# 65c02.net
KiCad netlist of a schematic drawn in Altium Designer
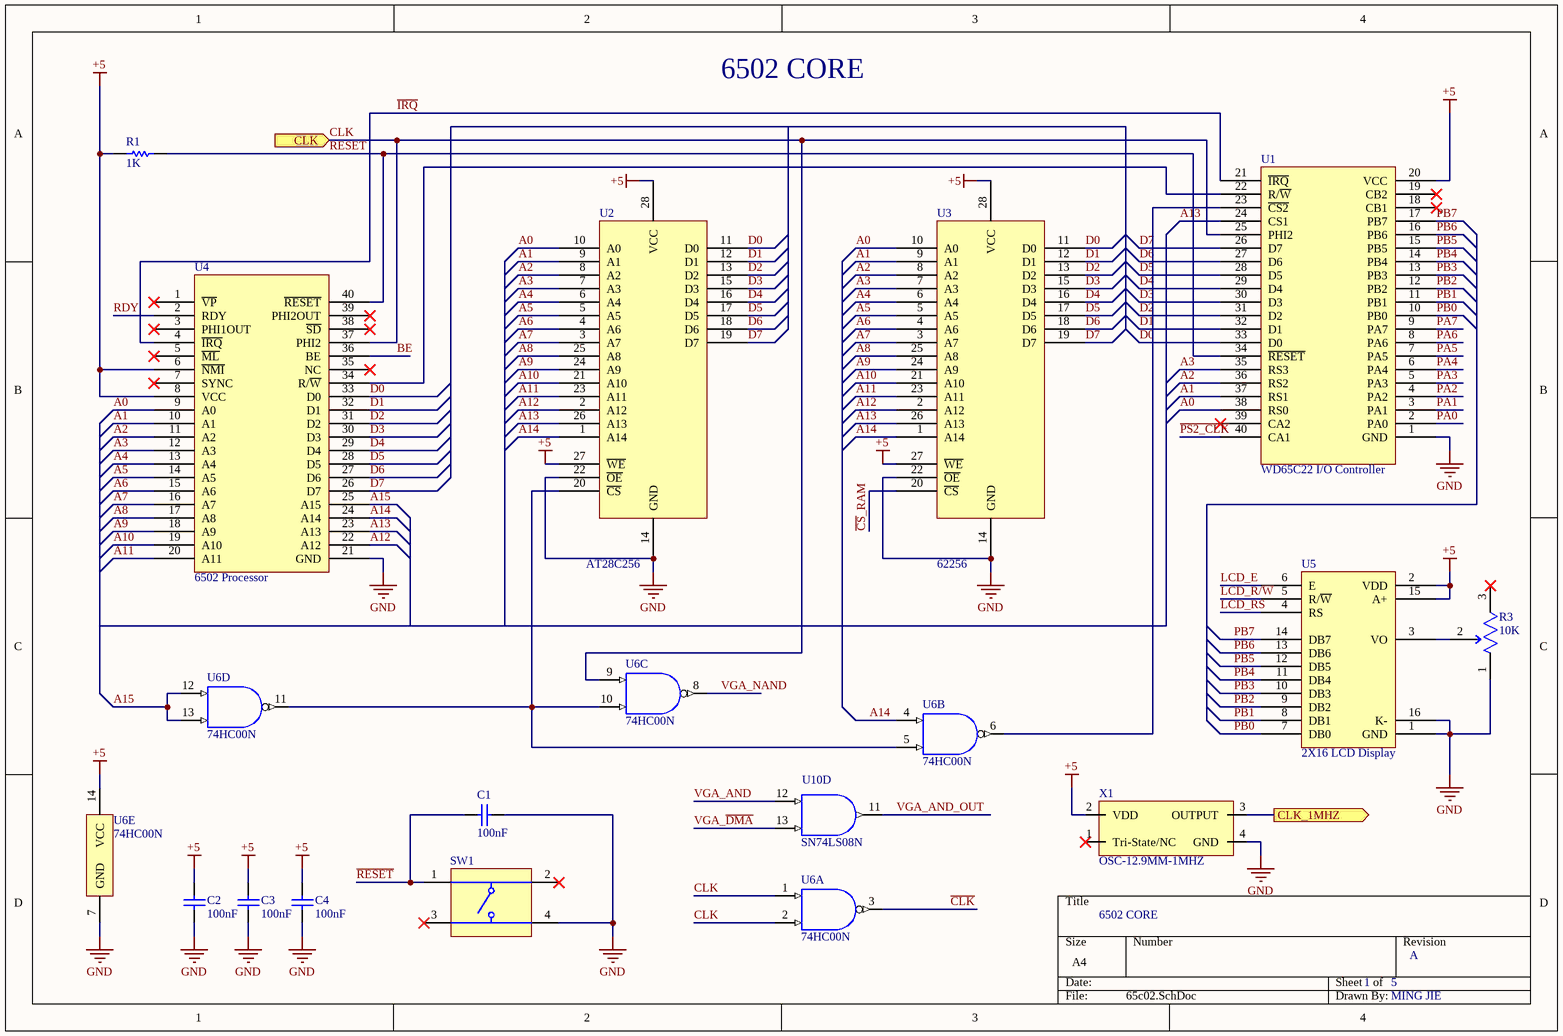
[diagram p0: 65c02.SchDoc]

(export (version "E")
  (design (tool "Eeschema 10.0.6"))
  (components
    (comp (ref "C1")
      (value "GRM21BR71H104KA01L")
      (footprint "CAPC2013X135X45ML10T25")
      (description "Chip Capacitor, 0.1 uF, +/- 10%, 50 V, -55 to 125 degC, 0805 (2012 Metric), RoHS, Tape and Reel")
      (fields
        (field (name "VOLTAGE") "50V")
        (field (name "CAPACITANCE") "100nF")
        (field (name "TOLERANCE") "10%")
      )
      (libsource (lib "Altium Content Vault") (part "CAP-NP-2"))
    )
    (comp (ref "C2")
      (value "GRM21BR71H104KA01L")
      (footprint "CAPC2013X135X45ML10T25")
      (description "Chip Capacitor, 0.1 uF, +/- 10%, 50 V, -55 to 125 degC, 0805 (2012 Metric), RoHS, Tape and Reel")
      (fields
        (field (name "VOLTAGE") "50V")
        (field (name "CAPACITANCE") "100nF")
        (field (name "TOLERANCE") "10%")
      )
      (libsource (lib "Altium Content Vault") (part "CAP-NP-2"))
    )
    (comp (ref "C3")
      (value "GRM21BR71H104KA01L")
      (footprint "CAPC2013X135X45ML10T25")
      (description "Chip Capacitor, 0.1 uF, +/- 10%, 50 V, -55 to 125 degC, 0805 (2012 Metric), RoHS, Tape and Reel")
      (fields
        (field (name "VOLTAGE") "50V")
        (field (name "CAPACITANCE") "100nF")
        (field (name "TOLERANCE") "10%")
      )
      (libsource (lib "Altium Content Vault") (part "CAP-NP-2"))
    )
    (comp (ref "C4")
      (value "GRM21BR71H104KA01L")
      (footprint "CAPC2013X135X45ML10T25")
      (description "Chip Capacitor, 0.1 uF, +/- 10%, 50 V, -55 to 125 degC, 0805 (2012 Metric), RoHS, Tape and Reel")
      (fields
        (field (name "VOLTAGE") "50V")
        (field (name "CAPACITANCE") "100nF")
        (field (name "TOLERANCE") "10%")
      )
      (libsource (lib "Altium Content Vault") (part "CAP-NP-2"))
    )
    (comp (ref "R1")
      (value "CRCW08051K00FKEA")
      (footprint "RESC2013X50X30NL20T20")
      (fields (field (name "MANUFACTURER") "Vishay Dale") (field (name "RESISTANCE") "1K"))
      (libsource (lib "Altium Content Vault") (part "RES"))
    )
    (comp (ref "R3")
      (value "3296W-1-103RLF")
      (footprint "FP-3296W-MFG")
      (description "TRIMMER 10K OHM 0.5W PC PIN TOP")
      (fields (field (name "RESISTANCE") "10K") (field (name "TOLERANCE") "10%"))
      (libsource (lib "Altium Content Vault") (part "194907ebf2981c0cdd5d9631a0af656"))
    )
    (comp (ref "SW1")
      (value "K2-1102SP-C4SC-04")
      (footprint "TECO-FSM4JSMA_V")
      (description "Swicth, SPST, 24 V, -35 to 85 degC, 4-Pin SMD, RoHS, Tape and Reel")
      (fields (field (name "MANUFACTURER") "TE Connectivity"))
      (libsource (lib "Altium Content Vault") (part "SW-SPST-4_A"))
    )
    (comp (ref "U1")
      (value "WD65C22 I/O Controller")
      (footprint "PDIP_40")
      (description "WD65C22 PDIP-40, I/O Controller")
      (libsource (lib "6502_lib") (part "WD65C22"))
    )
    (comp (ref "U2")
      (value "AT28C256")
      (footprint "DIP_28")
      (description "Paged Parallel EEPROM AT28C256")
      (libsource (lib "6502_lib") (part "AT28C256"))
    )
    (comp (ref "U3")
      (value "62256")
      (footprint "DIP_28")
      (description "32K x 8, SRAM")
      (libsource (lib "6502_lib") (part "62256"))
    )
    (comp (ref "U4")
      (value "6502 Processor")
      (footprint "PDIP_40")
      (description "WDC 6502 PDIP-40")
      (libsource (lib "6502_lib") (part "WDC65C02"))
    )
    (comp (ref "U5")
      (value "2X16 LCD Display")
      (footprint "LCD_2x16")
      (description "2X16 LCD Display, Parallel input")
      (libsource (lib "6502_lib") (part "LCM1602C"))
    )
    (comp (ref "U6")
      (value "74HC00N")
      (footprint "NXP-SOT27-1-14")
      (description "Quad 2-input NAND gate, CMOS, 2 to 6 V, -40 to 125 degC, 14-Pin DIP (SOT27-1), RoHS, Bulk")
      (fields (field (name "MANUFACTURER") "NXP Semiconductors"))
      (libsource (lib "Altium Content Vault") (part "NXP-74HC00N_HCT00N-DIP-14"))
    )
    (comp (ref "U10")
      (value "SN74LS08N")
      (footprint "N0014A")
      (description "Quadruple 2-Input Positive-AND Gates, N0014A, TUBE")
      (fields
        (field (name "MANUFACTURER") "Texas Instruments")
        (field (name "GENERIC PART NUMBER") "SN74LS08")
      )
      (libsource (lib "Altium Content Vault") (part "TI-AND-4-2IN-14"))
    )
    (comp (ref "X1")
      (value "OSC-12.9MM-1MHZ")
      (footprint "OSC_THT_12-9MM")
      (description "12.9MM x 12.9MM, 1MHz Can Oscillator")
      (libsource (lib "6502_lib") (part "OSC-12.9MM-1MHZ"))
    )
  )
  (nets
    (net (code "1") (name "+5") (class "Default")
      (node (ref "C2") (pin "1") (pinfunction "1_1") (pintype "passive"))
      (node (ref "C3") (pin "1") (pinfunction "1_1") (pintype "passive"))
      (node (ref "C4") (pin "1") (pinfunction "1_1") (pintype "passive"))
      (node (ref "R1") (pin "1") (pinfunction "1_1") (pintype "passive"))
      (node (ref "U1") (pin "20") (pinfunction "VCC_20") (pintype "passive"))
      (node (ref "U2") (pin "27") (pinfunction "~{WE}_27") (pintype "passive"))
      (node (ref "U2") (pin "28") (pinfunction "VCC_28") (pintype "passive"))
      (node (ref "U3") (pin "27") (pinfunction "~{WE}_27") (pintype "passive"))
      (node (ref "U3") (pin "28") (pinfunction "VCC_28") (pintype "passive"))
      (node (ref "U4") (pin "6") (pinfunction "~{NMI}_6") (pintype "passive"))
      (node (ref "U4") (pin "8") (pinfunction "VCC_8") (pintype "passive"))
      (node (ref "U5") (pin "15") (pinfunction "A+_15") (pintype "passive"))
      (node (ref "U5") (pin "2") (pinfunction "VDD_2") (pintype "passive"))
      (node (ref "U6") (pin "14") (pinfunction "VCC_14") (pintype "power_in"))
      (node (ref "X1") (pin "2") (pinfunction "VDD_2") (pintype "passive"))
    )
    (net (code "2") (name "/A0") (class "Default")
      (node (ref "U1") (pin "38") (pinfunction "RS0_38") (pintype "passive"))
      (node (ref "U2") (pin "10") (pinfunction "A0_10") (pintype "passive"))
      (node (ref "U3") (pin "10") (pinfunction "A0_10") (pintype "passive"))
      (node (ref "U4") (pin "9") (pinfunction "A0_9") (pintype "passive"))
    )
    (net (code "3") (name "/A1") (class "Default")
      (node (ref "U1") (pin "37") (pinfunction "RS1_37") (pintype "passive"))
      (node (ref "U2") (pin "9") (pinfunction "A1_9") (pintype "passive"))
      (node (ref "U3") (pin "9") (pinfunction "A1_9") (pintype "passive"))
      (node (ref "U4") (pin "10") (pinfunction "A1_10") (pintype "passive"))
    )
    (net (code "4") (name "/A2") (class "Default")
      (node (ref "U1") (pin "36") (pinfunction "RS2_36") (pintype "passive"))
      (node (ref "U2") (pin "8") (pinfunction "A2_8") (pintype "passive"))
      (node (ref "U3") (pin "8") (pinfunction "A2_8") (pintype "passive"))
      (node (ref "U4") (pin "11") (pinfunction "A2_11") (pintype "passive"))
    )
    (net (code "5") (name "/A3") (class "Default")
      (node (ref "U1") (pin "35") (pinfunction "RS3_35") (pintype "passive"))
      (node (ref "U2") (pin "7") (pinfunction "A3_7") (pintype "passive"))
      (node (ref "U3") (pin "7") (pinfunction "A3_7") (pintype "passive"))
      (node (ref "U4") (pin "12") (pinfunction "A3_12") (pintype "passive"))
    )
    (net (code "6") (name "/A4") (class "Default")
      (node (ref "U2") (pin "6") (pinfunction "A4_6") (pintype "passive"))
      (node (ref "U3") (pin "6") (pinfunction "A4_6") (pintype "passive"))
      (node (ref "U4") (pin "13") (pinfunction "A4_13") (pintype "passive"))
    )
    (net (code "7") (name "/A5") (class "Default")
      (node (ref "U2") (pin "5") (pinfunction "A5_5") (pintype "passive"))
      (node (ref "U3") (pin "5") (pinfunction "A5_5") (pintype "passive"))
      (node (ref "U4") (pin "14") (pinfunction "A5_14") (pintype "passive"))
    )
    (net (code "8") (name "/A6") (class "Default")
      (node (ref "U2") (pin "4") (pinfunction "A6_4") (pintype "passive"))
      (node (ref "U3") (pin "4") (pinfunction "A6_4") (pintype "passive"))
      (node (ref "U4") (pin "15") (pinfunction "A6_15") (pintype "passive"))
    )
    (net (code "9") (name "/A7") (class "Default")
      (node (ref "U2") (pin "3") (pinfunction "A7_3") (pintype "passive"))
      (node (ref "U3") (pin "3") (pinfunction "A7_3") (pintype "passive"))
      (node (ref "U4") (pin "16") (pinfunction "A7_16") (pintype "passive"))
    )
    (net (code "10") (name "/A8") (class "Default")
      (node (ref "U2") (pin "25") (pinfunction "A8_25") (pintype "passive"))
      (node (ref "U3") (pin "25") (pinfunction "A8_25") (pintype "passive"))
      (node (ref "U4") (pin "17") (pinfunction "A8_17") (pintype "passive"))
    )
    (net (code "11") (name "/A9") (class "Default")
      (node (ref "U2") (pin "24") (pinfunction "A9_24") (pintype "passive"))
      (node (ref "U3") (pin "24") (pinfunction "A9_24") (pintype "passive"))
      (node (ref "U4") (pin "18") (pinfunction "A9_18") (pintype "passive"))
    )
    (net (code "12") (name "/A10") (class "Default")
      (node (ref "U2") (pin "21") (pinfunction "A10_21") (pintype "passive"))
      (node (ref "U3") (pin "21") (pinfunction "A10_21") (pintype "passive"))
      (node (ref "U4") (pin "19") (pinfunction "A10_19") (pintype "passive"))
    )
    (net (code "13") (name "/A11") (class "Default")
      (node (ref "U2") (pin "23") (pinfunction "A11_23") (pintype "passive"))
      (node (ref "U3") (pin "23") (pinfunction "A11_23") (pintype "passive"))
      (node (ref "U4") (pin "20") (pinfunction "A11_20") (pintype "passive"))
    )
    (net (code "14") (name "/A12") (class "Default")
      (node (ref "U2") (pin "2") (pinfunction "A12_2") (pintype "passive"))
      (node (ref "U3") (pin "2") (pinfunction "A12_2") (pintype "passive"))
      (node (ref "U4") (pin "22") (pinfunction "A12_22") (pintype "passive"))
    )
    (net (code "15") (name "/A13") (class "Default")
      (node (ref "U1") (pin "24") (pinfunction "CS1_24") (pintype "passive"))
      (node (ref "U2") (pin "26") (pinfunction "A13_26") (pintype "passive"))
      (node (ref "U3") (pin "26") (pinfunction "A13_26") (pintype "passive"))
      (node (ref "U4") (pin "23") (pinfunction "A13_23") (pintype "passive"))
    )
    (net (code "16") (name "/A14") (class "Default")
      (node (ref "U2") (pin "1") (pinfunction "A14_1") (pintype "passive"))
      (node (ref "U3") (pin "1") (pinfunction "A14_1") (pintype "passive"))
      (node (ref "U4") (pin "24") (pinfunction "A14_24") (pintype "passive"))
      (node (ref "U6") (pin "4") (pinfunction "2A_4") (pintype "input"))
    )
    (net (code "17") (name "/A15") (class "Default")
      (node (ref "U4") (pin "25") (pinfunction "A15_25") (pintype "passive"))
      (node (ref "U6") (pin "12") (pinfunction "4A_12") (pintype "input"))
      (node (ref "U6") (pin "13") (pinfunction "4B_13") (pintype "input"))
    )
    (net (code "18") (name "/BE") (class "Default")
      (node (ref "U4") (pin "36") (pinfunction "BE_36") (pintype "passive"))
    )
    (net (code "19") (name "/CLK") (class "Default")
      (node (ref "U1") (pin "25") (pinfunction "PHI2_25") (pintype "passive"))
      (node (ref "U4") (pin "37") (pinfunction "PHI2_37") (pintype "passive"))
      (node (ref "U6") (pin "1") (pinfunction "1A_1") (pintype "input"))
      (node (ref "U6") (pin "2") (pinfunction "1B_2") (pintype "input"))
      (node (ref "U6") (pin "9") (pinfunction "3A_9") (pintype "input"))
    )
    (net (code "20") (name "/CLK_1MHZ") (class "Default")
      (node (ref "X1") (pin "3") (pinfunction "OUTPUT_3") (pintype "passive"))
    )
    (net (code "21") (name "/D0") (class "Default")
      (node (ref "U1") (pin "33") (pinfunction "D0_33") (pintype "passive"))
      (node (ref "U2") (pin "11") (pinfunction "D0_11") (pintype "passive"))
      (node (ref "U3") (pin "11") (pinfunction "D0_11") (pintype "passive"))
      (node (ref "U4") (pin "33") (pinfunction "D0_33") (pintype "passive"))
    )
    (net (code "22") (name "/D1") (class "Default")
      (node (ref "U1") (pin "32") (pinfunction "D1_32") (pintype "passive"))
      (node (ref "U2") (pin "12") (pinfunction "D1_12") (pintype "passive"))
      (node (ref "U3") (pin "12") (pinfunction "D1_12") (pintype "passive"))
      (node (ref "U4") (pin "32") (pinfunction "D1_32") (pintype "passive"))
    )
    (net (code "23") (name "/D2") (class "Default")
      (node (ref "U1") (pin "31") (pinfunction "D2_31") (pintype "passive"))
      (node (ref "U2") (pin "13") (pinfunction "D2_13") (pintype "passive"))
      (node (ref "U3") (pin "13") (pinfunction "D2_13") (pintype "passive"))
      (node (ref "U4") (pin "31") (pinfunction "D2_31") (pintype "passive"))
    )
    (net (code "24") (name "/D3") (class "Default")
      (node (ref "U1") (pin "30") (pinfunction "D3_30") (pintype "passive"))
      (node (ref "U2") (pin "15") (pinfunction "D3_15") (pintype "passive"))
      (node (ref "U3") (pin "15") (pinfunction "D3_15") (pintype "passive"))
      (node (ref "U4") (pin "30") (pinfunction "D3_30") (pintype "passive"))
    )
    (net (code "25") (name "/D4") (class "Default")
      (node (ref "U1") (pin "29") (pinfunction "D4_29") (pintype "passive"))
      (node (ref "U2") (pin "16") (pinfunction "D4_16") (pintype "passive"))
      (node (ref "U3") (pin "16") (pinfunction "D4_16") (pintype "passive"))
      (node (ref "U4") (pin "29") (pinfunction "D4_29") (pintype "passive"))
    )
    (net (code "26") (name "/D5") (class "Default")
      (node (ref "U1") (pin "28") (pinfunction "D5_28") (pintype "passive"))
      (node (ref "U2") (pin "17") (pinfunction "D5_17") (pintype "passive"))
      (node (ref "U3") (pin "17") (pinfunction "D5_17") (pintype "passive"))
      (node (ref "U4") (pin "28") (pinfunction "D5_28") (pintype "passive"))
    )
    (net (code "27") (name "/D6") (class "Default")
      (node (ref "U1") (pin "27") (pinfunction "D6_27") (pintype "passive"))
      (node (ref "U2") (pin "18") (pinfunction "D6_18") (pintype "passive"))
      (node (ref "U3") (pin "18") (pinfunction "D6_18") (pintype "passive"))
      (node (ref "U4") (pin "27") (pinfunction "D6_27") (pintype "passive"))
    )
    (net (code "28") (name "/D7") (class "Default")
      (node (ref "U1") (pin "26") (pinfunction "D7_26") (pintype "passive"))
      (node (ref "U2") (pin "19") (pinfunction "D7_19") (pintype "passive"))
      (node (ref "U3") (pin "19") (pinfunction "D7_19") (pintype "passive"))
      (node (ref "U4") (pin "26") (pinfunction "D7_26") (pintype "passive"))
    )
    (net (code "29") (name "/LCD_E") (class "Default")
      (node (ref "U5") (pin "6") (pinfunction "E_6") (pintype "passive"))
    )
    (net (code "30") (name "/LCD_RS") (class "Default")
      (node (ref "U5") (pin "4") (pinfunction "RS_4") (pintype "passive"))
    )
    (net (code "31") (name "/LCD_R{slash}~{W}") (class "Default")
      (node (ref "U5") (pin "5") (pinfunction "R/~{W}_5") (pintype "passive"))
    )
    (net (code "32") (name "/PA0") (class "Default")
      (node (ref "U1") (pin "2") (pinfunction "PA0_2") (pintype "passive"))
    )
    (net (code "33") (name "/PA1") (class "Default")
      (node (ref "U1") (pin "3") (pinfunction "PA1_3") (pintype "passive"))
    )
    (net (code "34") (name "/PA2") (class "Default")
      (node (ref "U1") (pin "4") (pinfunction "PA2_4") (pintype "passive"))
    )
    (net (code "35") (name "/PA3") (class "Default")
      (node (ref "U1") (pin "5") (pinfunction "PA3_5") (pintype "passive"))
    )
    (net (code "36") (name "/PA4") (class "Default")
      (node (ref "U1") (pin "6") (pinfunction "PA4_6") (pintype "passive"))
    )
    (net (code "37") (name "/PA5") (class "Default")
      (node (ref "U1") (pin "7") (pinfunction "PA5_7") (pintype "passive"))
    )
    (net (code "38") (name "/PA6") (class "Default")
      (node (ref "U1") (pin "8") (pinfunction "PA6_8") (pintype "passive"))
    )
    (net (code "39") (name "/PA7") (class "Default")
      (node (ref "U1") (pin "9") (pinfunction "PA7_9") (pintype "passive"))
    )
    (net (code "40") (name "/PB0") (class "Default")
      (node (ref "U1") (pin "10") (pinfunction "PB0_10") (pintype "passive"))
      (node (ref "U5") (pin "7") (pinfunction "DB0_7") (pintype "passive"))
    )
    (net (code "41") (name "/PB1") (class "Default")
      (node (ref "U1") (pin "11") (pinfunction "PB1_11") (pintype "passive"))
      (node (ref "U5") (pin "8") (pinfunction "DB1_8") (pintype "passive"))
    )
    (net (code "42") (name "/PB2") (class "Default")
      (node (ref "U1") (pin "12") (pinfunction "PB2_12") (pintype "passive"))
      (node (ref "U5") (pin "9") (pinfunction "DB2_9") (pintype "passive"))
    )
    (net (code "43") (name "/PB3") (class "Default")
      (node (ref "U1") (pin "13") (pinfunction "PB3_13") (pintype "passive"))
      (node (ref "U5") (pin "10") (pinfunction "DB3_10") (pintype "passive"))
    )
    (net (code "44") (name "/PB4") (class "Default")
      (node (ref "U1") (pin "14") (pinfunction "PB4_14") (pintype "passive"))
      (node (ref "U5") (pin "11") (pinfunction "DB4_11") (pintype "passive"))
    )
    (net (code "45") (name "/PB5") (class "Default")
      (node (ref "U1") (pin "15") (pinfunction "PB5_15") (pintype "passive"))
      (node (ref "U5") (pin "12") (pinfunction "DB5_12") (pintype "passive"))
    )
    (net (code "46") (name "/PB6") (class "Default")
      (node (ref "U1") (pin "16") (pinfunction "PB6_16") (pintype "passive"))
      (node (ref "U5") (pin "13") (pinfunction "DB6_13") (pintype "passive"))
    )
    (net (code "47") (name "/PB7") (class "Default")
      (node (ref "U1") (pin "17") (pinfunction "PB7_17") (pintype "passive"))
      (node (ref "U5") (pin "14") (pinfunction "DB7_14") (pintype "passive"))
    )
    (net (code "48") (name "/RDY") (class "Default")
      (node (ref "U4") (pin "2") (pinfunction "RDY_2") (pintype "passive"))
    )
    (net (code "49") (name "/VGA_AND") (class "Default")
      (node (ref "U10") (pin "12") (pinfunction "4A_12") (pintype "input"))
    )
    (net (code "50") (name "/VGA_AND_OUT") (class "Default")
      (node (ref "U10") (pin "11") (pinfunction "4Y_11") (pintype "output"))
    )
    (net (code "51") (name "/VGA_NAND") (class "Default")
      (node (ref "U6") (pin "8") (pinfunction "~{3Y}_8") (pintype "output"))
    )
    (net (code "52") (name "/VGA_~{DMA}") (class "Default")
      (node (ref "U10") (pin "13") (pinfunction "4B_13") (pintype "input"))
    )
    (net (code "53") (name "/~{CLK}") (class "Default")
      (node (ref "U6") (pin "3") (pinfunction "~{1Y}_3") (pintype "output"))
    )
    (net (code "54") (name "/~{CS}_RAM") (class "Default")
      (node (ref "U3") (pin "20") (pinfunction "~{CS}_20") (pintype "passive"))
    )
    (net (code "55") (name "/~{IRQ}") (class "Default")
      (node (ref "U1") (pin "21") (pinfunction "~{IRQ}_21") (pintype "passive"))
      (node (ref "U4") (pin "4") (pinfunction "~{IRQ}_4") (pintype "passive"))
    )
    (net (code "56") (name "/~{PS2_CLK}") (class "Default")
      (node (ref "U1") (pin "40") (pinfunction "CA1_40") (pintype "passive"))
    )
    (net (code "57") (name "/~{RESET}") (class "Default")
      (node (ref "C1") (pin "2") (pinfunction "2_2") (pintype "passive"))
      (node (ref "R1") (pin "2") (pinfunction "2_2") (pintype "passive"))
      (node (ref "SW1") (pin "1") (pinfunction "1_1") (pintype "passive"))
      (node (ref "U1") (pin "34") (pinfunction "~{RESET}_34") (pintype "passive"))
      (node (ref "U4") (pin "40") (pinfunction "~{RESET}_40") (pintype "passive"))
    )
    (net (code "58") (name "GND") (class "Default")
      (node (ref "C1") (pin "1") (pinfunction "1_1") (pintype "passive"))
      (node (ref "C2") (pin "2") (pinfunction "2_2") (pintype "passive"))
      (node (ref "C3") (pin "2") (pinfunction "2_2") (pintype "passive"))
      (node (ref "C4") (pin "2") (pinfunction "2_2") (pintype "passive"))
      (node (ref "R3") (pin "1") (pinfunction "CCW_1") (pintype "passive"))
      (node (ref "SW1") (pin "4") (pinfunction "4_4") (pintype "passive"))
      (node (ref "U1") (pin "1") (pinfunction "GND_1") (pintype "passive"))
      (node (ref "U2") (pin "14") (pinfunction "GND_14") (pintype "passive"))
      (node (ref "U2") (pin "22") (pinfunction "~{OE}_22") (pintype "passive"))
      (node (ref "U3") (pin "14") (pinfunction "GND_14") (pintype "passive"))
      (node (ref "U3") (pin "22") (pinfunction "~{OE}_22") (pintype "passive"))
      (node (ref "U4") (pin "21") (pinfunction "GND_21") (pintype "passive"))
      (node (ref "U5") (pin "1") (pinfunction "GND_1") (pintype "passive"))
      (node (ref "U5") (pin "16") (pinfunction "K-_16") (pintype "passive"))
      (node (ref "U6") (pin "7") (pinfunction "GND_7") (pintype "power_in"))
      (node (ref "X1") (pin "4") (pinfunction "GND_4") (pintype "passive"))
    )
    (net (code "59") (name "Net-(R3-WIPER)") (class "Default")
      (node (ref "R3") (pin "2") (pinfunction "WIPER_2") (pintype "passive"))
      (node (ref "U5") (pin "3") (pinfunction "VO_3") (pintype "passive"))
    )
    (net (code "60") (name "Net-(U1-R{slash}~{W})") (class "Default")
      (node (ref "U1") (pin "22") (pinfunction "R/~{W}_22") (pintype "passive"))
      (node (ref "U4") (pin "34") (pinfunction "R/~{W}_34") (pintype "passive"))
    )
    (net (code "61") (name "Net-(U1-~{CS2})") (class "Default")
      (node (ref "U1") (pin "23") (pinfunction "~{CS2}_23") (pintype "passive"))
      (node (ref "U6") (pin "6") (pinfunction "~{2Y}_6") (pintype "output"))
    )
    (net (code "62") (name "Net-(U2-~{CS})") (class "Default")
      (node (ref "U2") (pin "20") (pinfunction "~{CS}_20") (pintype "passive"))
      (node (ref "U6") (pin "10") (pinfunction "3B_10") (pintype "input"))
      (node (ref "U6") (pin "11") (pinfunction "~{4Y}_11") (pintype "output"))
      (node (ref "U6") (pin "5") (pinfunction "2B_5") (pintype "input"))
    )
    (net (code "63") (name "unconnected-(R3-CW-Pad3)") (class "Default")
      (node (ref "R3") (pin "3") (pinfunction "CW_3") (pintype "passive+no_connect"))
    )
    (net (code "64") (name "unconnected-(SW1-Pad2)") (class "Default")
      (node (ref "SW1") (pin "2") (pinfunction "2_2") (pintype "passive+no_connect"))
    )
    (net (code "65") (name "unconnected-(SW1-Pad3)") (class "Default")
      (node (ref "SW1") (pin "3") (pinfunction "3_3") (pintype "passive+no_connect"))
    )
    (net (code "66") (name "unconnected-(U1-CA2-Pad39)") (class "Default")
      (node (ref "U1") (pin "39") (pinfunction "CA2_39") (pintype "passive+no_connect"))
    )
    (net (code "67") (name "unconnected-(U1-CB1-Pad18)") (class "Default")
      (node (ref "U1") (pin "18") (pinfunction "CB1_18") (pintype "passive+no_connect"))
    )
    (net (code "68") (name "unconnected-(U1-CB2-Pad19)") (class "Default")
      (node (ref "U1") (pin "19") (pinfunction "CB2_19") (pintype "passive+no_connect"))
    )
    (net (code "69") (name "unconnected-(U4-NC-Pad35)") (class "Default")
      (node (ref "U4") (pin "35") (pinfunction "NC_35") (pintype "passive+no_connect"))
    )
    (net (code "70") (name "unconnected-(U4-PHI1OUT-Pad3)") (class "Default")
      (node (ref "U4") (pin "3") (pinfunction "PHI1OUT_3") (pintype "passive+no_connect"))
    )
    (net (code "71") (name "unconnected-(U4-PHI2OUT-Pad39)") (class "Default")
      (node (ref "U4") (pin "39") (pinfunction "PHI2OUT_39") (pintype "passive+no_connect"))
    )
    (net (code "72") (name "unconnected-(U4-SYNC-Pad7)") (class "Default")
      (node (ref "U4") (pin "7") (pinfunction "SYNC_7") (pintype "passive+no_connect"))
    )
    (net (code "73") (name "unconnected-(U4-~{ML}-Pad5)") (class "Default")
      (node (ref "U4") (pin "5") (pinfunction "~{ML}_5") (pintype "passive+no_connect"))
    )
    (net (code "74") (name "unconnected-(U4-~{SD}-Pad38)") (class "Default")
      (node (ref "U4") (pin "38") (pinfunction "~{SD}_38") (pintype "passive+no_connect"))
    )
    (net (code "75") (name "unconnected-(U4-~{VP}-Pad1)") (class "Default")
      (node (ref "U4") (pin "1") (pinfunction "~{VP}_1") (pintype "passive+no_connect"))
    )
    (net (code "76") (name "unconnected-(X1-Tri-State{slash}NC-Pad1)") (class "Default")
      (node (ref "X1") (pin "1") (pinfunction "Tri-State/NC_1") (pintype "passive+no_connect"))
    )
  )
)
